# Schematic_v20.net
KiCad netlist of a schematic drawn in EAGLE
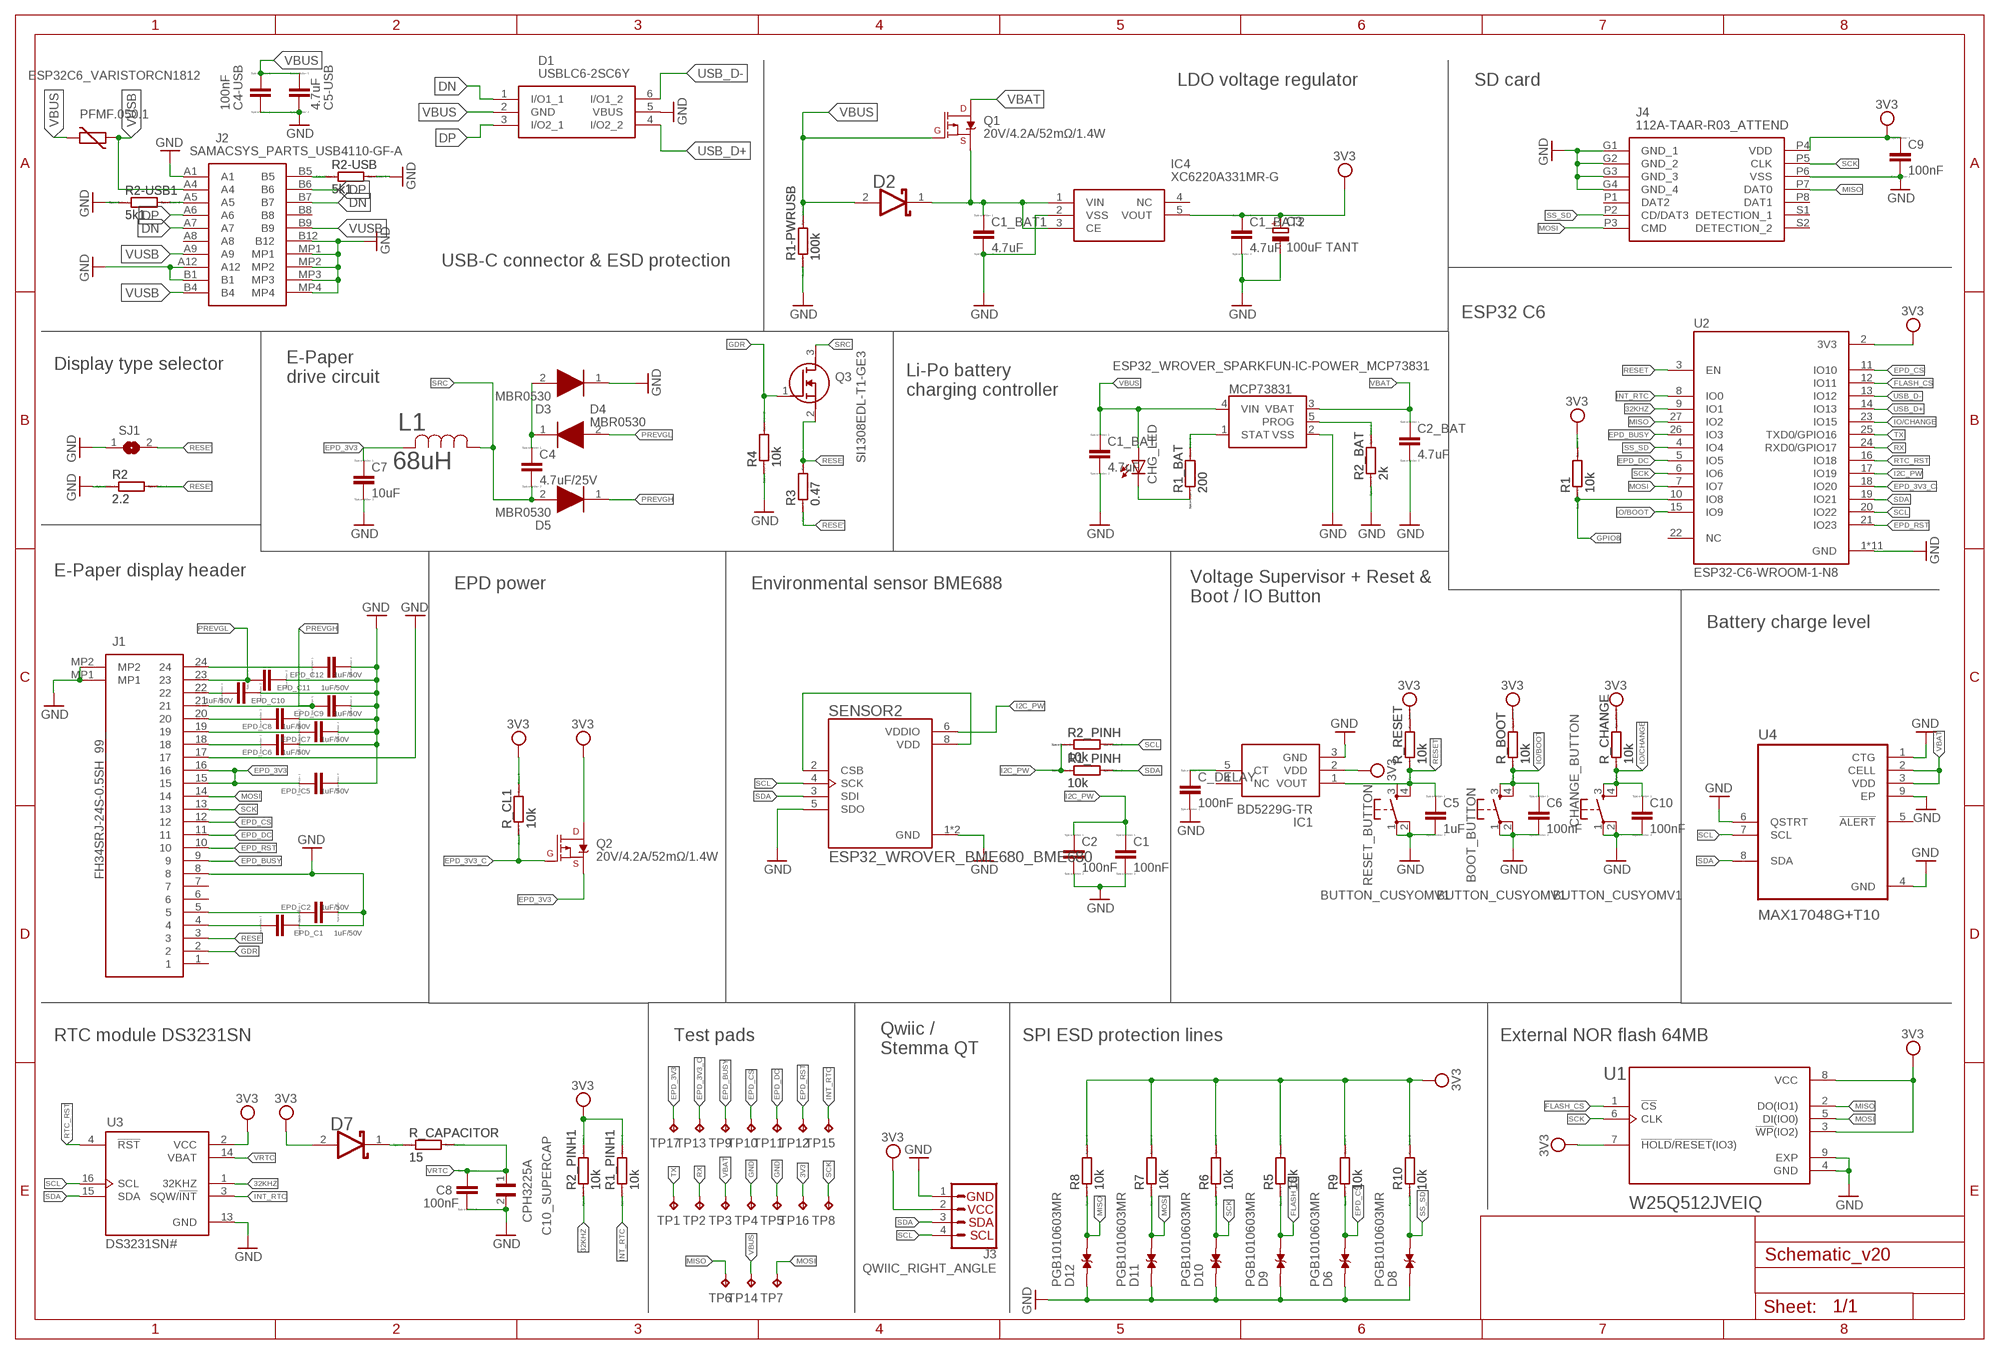
[diagram p0: schematic, sheet 1]

(export (version "E")
  (design (tool "Eeschema 10.0.6"))
  (components
    (comp (ref "BOOT_BUTTON")
      (value "BUTTON_CUSYOMV1")
      (footprint "eagle-import:MYBUTTON")
      (libsource (lib "eagle-import") (part "BUTTON_CUSYOMV1"))
    )
    (comp (ref "C1")
      (value "100nF")
      (footprint "eagle-import:EAGLE-LTSPICE_C0402")
      (libsource (lib "eagle-import") (part "EAGLE-LTSPICE_CC0402"))
    )
    (comp (ref "C1_BAT")
      (value "4.7uF")
      (footprint "eagle-import:EAGLE-LTSPICE_C0402")
      (libsource (lib "eagle-import") (part "EAGLE-LTSPICE_CC0402"))
    )
    (comp (ref "C1_BAT1")
      (value "4.7uF")
      (footprint "eagle-import:ESP32_WROVER_EAGLE-LTSPICE_C0402")
      (libsource (lib "eagle-import") (part "ESP32_WROVER_EAGLE-LTSPICE_CC0402"))
    )
    (comp (ref "C1_BAT2")
      (value "4.7uF")
      (footprint "eagle-import:ESP32_WROVER_EAGLE-LTSPICE_C0402")
      (libsource (lib "eagle-import") (part "ESP32_WROVER_EAGLE-LTSPICE_CC0402"))
    )
    (comp (ref "C2")
      (value "100nF")
      (footprint "eagle-import:EAGLE-LTSPICE_C0402")
      (libsource (lib "eagle-import") (part "EAGLE-LTSPICE_CC0402"))
    )
    (comp (ref "C2_BAT")
      (value "4.7uF")
      (footprint "eagle-import:EAGLE-LTSPICE_C0402")
      (libsource (lib "eagle-import") (part "EAGLE-LTSPICE_CC0402"))
    )
    (comp (ref "C3")
      (value "100uF TANT")
      (footprint "eagle-import:RCL_CT3528")
      (libsource (lib "eagle-import") (part "RCL_CPOL-EUCT3528"))
    )
    (comp (ref "C4")
      (value "4.7uF/25V")
      (footprint "eagle-import:EAGLE-LTSPICE_C0402")
      (libsource (lib "eagle-import") (part "EAGLE-LTSPICE_CC0402"))
    )
    (comp (ref "C4-USB")
      (value "100nF")
      (footprint "eagle-import:ESP32_WROVER_EAGLE-LTSPICE_C0402")
      (libsource (lib "eagle-import") (part "ESP32_WROVER_EAGLE-LTSPICE_CC0402"))
    )
    (comp (ref "C5")
      (value "1uF")
      (footprint "eagle-import:EAGLE-LTSPICE_C0402")
      (libsource (lib "eagle-import") (part "EAGLE-LTSPICE_CC0402"))
    )
    (comp (ref "C5-USB")
      (value "4.7uF")
      (footprint "eagle-import:ESP32_WROVER_EAGLE-LTSPICE_C0402")
      (libsource (lib "eagle-import") (part "ESP32_WROVER_EAGLE-LTSPICE_CC0402"))
    )
    (comp (ref "C6")
      (value "100nF")
      (footprint "eagle-import:EAGLE-LTSPICE_C0402")
      (libsource (lib "eagle-import") (part "EAGLE-LTSPICE_CC0402"))
    )
    (comp (ref "C7")
      (value "10uF")
      (footprint "eagle-import:EAGLE-LTSPICE_C0402")
      (libsource (lib "eagle-import") (part "EAGLE-LTSPICE_CC0402"))
    )
    (comp (ref "C8")
      (value "100nF")
      (footprint "eagle-import:EAGLE-LTSPICE_C0402")
      (libsource (lib "eagle-import") (part "EAGLE-LTSPICE_CC0402"))
    )
    (comp (ref "C9")
      (value "100nF")
      (footprint "eagle-import:EAGLE-LTSPICE_C0402")
      (libsource (lib "eagle-import") (part "EAGLE-LTSPICE_CC0402"))
    )
    (comp (ref "C10")
      (value "100nF")
      (footprint "eagle-import:EAGLE-LTSPICE_C0402")
      (libsource (lib "eagle-import") (part "EAGLE-LTSPICE_CC0402"))
    )
    (comp (ref "C10_SUPERCAP")
      (value "CPH3225A")
      (footprint "eagle-import:CAPCP3225X100N")
      (fields (field (name "MF") "Seiko Instruments"))
      (libsource (lib "eagle-import") (part "CPH3225A"))
    )
    (comp (ref "CHANGE_BUTTON")
      (value "BUTTON_CUSYOMV1")
      (footprint "eagle-import:MYBUTTON")
      (libsource (lib "eagle-import") (part "BUTTON_CUSYOMV1"))
    )
    (comp (ref "CHG_LED")
      (value "ADAFRUIT_LEDCHIP-LED0603")
      (footprint "eagle-import:ADAFRUIT_CHIP-LED0603")
      (libsource (lib "eagle-import") (part "ADAFRUIT_LEDCHIP-LED0603"))
    )
    (comp (ref "C_DELAY")
      (value "100nF")
      (footprint "eagle-import:EAGLE-LTSPICE_C0402")
      (libsource (lib "eagle-import") (part "EAGLE-LTSPICE_CC0402"))
    )
    (comp (ref "D1")
      (value "USBLC6-2SC6Y")
      (footprint "eagle-import:SOT95P280X145-6N")
      (fields (field (name "MF") "STMicroelectronics"))
      (libsource (lib "eagle-import") (part "USBLC6-2SC6Y"))
    )
    (comp (ref "D2")
      (value "ESP32_WROVER_AVX---SD0805S020S1R0_AVX_SD0805S020S1R0_0_0AVX_SD0805S020S1R0_0_0")
      (footprint "eagle-import:ESP32_WROVER_AVX---SD0805S020S1R0_AVX_SD0805S020S1R0_0")
      (fields
        (field (name "DIGIKEY_PART_NUMBER") "478-7800-1-ND")
        (field (name "MF") "AVX")
        (field (name "MOUSER_PART_NUMBER") "581-SD0805S020S1R0")
      )
      (libsource (lib "eagle-import") (part "ESP32_WROVER_AVX---SD0805S020S1R0_AVX_SD0805S020S1R0_0_0AVX_SD0805S020S1R0_0_0"))
    )
    (comp (ref "D3")
      (value "MBR0530")
      (footprint "eagle-import:SOD3716X135N")
      (fields (field (name "MF") "ON Semiconductor"))
      (libsource (lib "eagle-import") (part "MBR0530"))
    )
    (comp (ref "D4")
      (value "MBR0530")
      (footprint "eagle-import:SOD3716X135N")
      (fields (field (name "MF") "ON Semiconductor"))
      (libsource (lib "eagle-import") (part "MBR0530"))
    )
    (comp (ref "D5")
      (value "MBR0530")
      (footprint "eagle-import:SOD3716X135N")
      (fields (field (name "MF") "ON Semiconductor"))
      (libsource (lib "eagle-import") (part "MBR0530"))
    )
    (comp (ref "D6")
      (value "PGB1010603MR")
      (footprint "eagle-import:DIOC1608X36N")
      (fields (field (name "MF") "Littelfuse Inc."))
      (libsource (lib "eagle-import") (part "PGB1010603MR"))
    )
    (comp (ref "D7")
      (value "ESP32_WROVER_AVX---SD0805S020S1R0_AVX_SD0805S020S1R0_0_0AVX_SD0805S020S1R0_0_0")
      (footprint "eagle-import:ESP32_WROVER_AVX---SD0805S020S1R0_AVX_SD0805S020S1R0_0")
      (fields
        (field (name "DIGIKEY_PART_NUMBER") "478-7800-1-ND")
        (field (name "MF") "AVX")
        (field (name "MOUSER_PART_NUMBER") "581-SD0805S020S1R0")
      )
      (libsource (lib "eagle-import") (part "ESP32_WROVER_AVX---SD0805S020S1R0_AVX_SD0805S020S1R0_0_0AVX_SD0805S020S1R0_0_0"))
    )
    (comp (ref "D8")
      (value "PGB1010603MR")
      (footprint "eagle-import:DIOC1608X36N")
      (fields (field (name "MF") "Littelfuse Inc."))
      (libsource (lib "eagle-import") (part "PGB1010603MR"))
    )
    (comp (ref "D9")
      (value "PGB1010603MR")
      (footprint "eagle-import:DIOC1608X36N")
      (fields (field (name "MF") "Littelfuse Inc."))
      (libsource (lib "eagle-import") (part "PGB1010603MR"))
    )
    (comp (ref "D10")
      (value "PGB1010603MR")
      (footprint "eagle-import:DIOC1608X36N")
      (fields (field (name "MF") "Littelfuse Inc."))
      (libsource (lib "eagle-import") (part "PGB1010603MR"))
    )
    (comp (ref "D11")
      (value "PGB1010603MR")
      (footprint "eagle-import:DIOC1608X36N")
      (fields (field (name "MF") "Littelfuse Inc."))
      (libsource (lib "eagle-import") (part "PGB1010603MR"))
    )
    (comp (ref "D12")
      (value "PGB1010603MR")
      (footprint "eagle-import:DIOC1608X36N")
      (fields (field (name "MF") "Littelfuse Inc."))
      (libsource (lib "eagle-import") (part "PGB1010603MR"))
    )
    (comp (ref "EPD_C1")
      (value "1uF/50V")
      (footprint "eagle-import:EAGLE-LTSPICE_C0402")
      (libsource (lib "eagle-import") (part "EAGLE-LTSPICE_CC0402"))
    )
    (comp (ref "EPD_C2")
      (value "1uF/50V")
      (footprint "eagle-import:EAGLE-LTSPICE_C0402")
      (libsource (lib "eagle-import") (part "EAGLE-LTSPICE_CC0402"))
    )
    (comp (ref "EPD_C5")
      (value "1uF/50V")
      (footprint "eagle-import:EAGLE-LTSPICE_C0402")
      (libsource (lib "eagle-import") (part "EAGLE-LTSPICE_CC0402"))
    )
    (comp (ref "EPD_C6")
      (value "1uF/50V")
      (footprint "eagle-import:EAGLE-LTSPICE_C0402")
      (libsource (lib "eagle-import") (part "EAGLE-LTSPICE_CC0402"))
    )
    (comp (ref "EPD_C7")
      (value "1uF/50V")
      (footprint "eagle-import:EAGLE-LTSPICE_C0402")
      (libsource (lib "eagle-import") (part "EAGLE-LTSPICE_CC0402"))
    )
    (comp (ref "EPD_C8")
      (value "1uF/50V")
      (footprint "eagle-import:EAGLE-LTSPICE_C0402")
      (libsource (lib "eagle-import") (part "EAGLE-LTSPICE_CC0402"))
    )
    (comp (ref "EPD_C9")
      (value "1uF/50V")
      (footprint "eagle-import:EAGLE-LTSPICE_C0402")
      (libsource (lib "eagle-import") (part "EAGLE-LTSPICE_CC0402"))
    )
    (comp (ref "EPD_C10")
      (value "1uF/50V")
      (footprint "eagle-import:EAGLE-LTSPICE_C0402")
      (libsource (lib "eagle-import") (part "EAGLE-LTSPICE_CC0402"))
    )
    (comp (ref "EPD_C11")
      (value "1uF/50V")
      (footprint "eagle-import:EAGLE-LTSPICE_C0402")
      (libsource (lib "eagle-import") (part "EAGLE-LTSPICE_CC0402"))
    )
    (comp (ref "EPD_C12")
      (value "1uF/50V")
      (footprint "eagle-import:EAGLE-LTSPICE_C0402")
      (libsource (lib "eagle-import") (part "EAGLE-LTSPICE_CC0402"))
    )
    (comp (ref "IC1")
      (value "BD5229G-TR")
      (footprint "eagle-import:SOT95P280X125-5N")
      (fields (field (name "MOUSER_PART_NUMBER") "755-BD5229G-TR"))
      (libsource (lib "eagle-import") (part "BD5229G-TR"))
    )
    (comp (ref "IC4")
      (value "XC6220A331MR-G")
      (footprint "eagle-import:SOT95P280X120-5N")
      (fields (field (name "MOUSER_PART_NUMBER") "865-XC6220A331MR-G"))
      (libsource (lib "eagle-import") (part "XC6220A331MR-G"))
    )
    (comp (ref "J1")
      (value "FH34SRJ-24S-0.5SH_99_")
      (footprint "eagle-import:FH34SRJ24S05SH99")
      (fields
        (field (name "MANUFACTURER_PART_NUMBER") "FH34SRJ-24S-0.5SH(99)")
        (field (name "MOUSER_PART_NUMBER") "798-FH34SRJ24S05SH99")
      )
      (libsource (lib "eagle-import") (part "FH34SRJ-24S-0.5SH_99_"))
    )
    (comp (ref "J2")
      (value "SAMACSYS_PARTS_USB4110-GF-A")
      (footprint "eagle-import:SAMACSYS_PARTS_USB4110GFA")
      (fields
        (field (name "MANUFACTURER_PART_NUMBER") "USB4110-GF-A")
        (field (name "MOUSER_PART_NUMBER") "640-USB4110-GF-A")
      )
      (libsource (lib "eagle-import") (part "SAMACSYS_PARTS_USB4110-GF-A"))
    )
    (comp (ref "J3")
      (value "QWIIC_RIGHT_ANGLE")
      (footprint "eagle-import:JST04_1MM_RA")
      (libsource (lib "eagle-import") (part "QWIIC_CONNECTORJS-1MM"))
    )
    (comp (ref "J4")
      (value "112A-TAAR-R03_ATTEND")
      (footprint "eagle-import:112ATAARR03ATTEND")
      (fields (field (name "MANUFACTURER_PART_NUMBER") "112A-TAAR-R03 ATTEND"))
      (libsource (lib "eagle-import") (part "112A-TAAR-R03_ATTEND"))
    )
    (comp (ref "L1")
      (value "68uH")
      (footprint "eagle-import:IND_4828-WE-TPC_WRE")
      (fields
        (field (name "MANUFACTURER_PART_NUMBER") "744043680")
        (field (name "COPYRIGHT") "Copyright (C) 2024 Ultra Librarian. All rights reserved.")
      )
      (libsource (lib "eagle-import") (part "744043680IND_4828-WE-TPC_WRE"))
    )
    (comp (ref "MCP73831")
      (value "ESP32_WROVER_SPARKFUN-IC-POWER_MCP73831")
      (footprint "eagle-import:ESP32_WROVER_SPARKFUN-IC-POWER_SOT23-5")
      (libsource (lib "eagle-import") (part "ESP32_WROVER_SPARKFUN-IC-POWER_MCP73831"))
    )
    (comp (ref "PFMF.050.1")
      (value "ESP32C6_VARISTORCN1812")
      (footprint "eagle-import:ESP32C6_VARISTOR_CT_CN1812")
      (libsource (lib "eagle-import") (part "ESP32C6_VARISTORCN1812"))
    )
    (comp (ref "Q1")
      (value "20V/4.2A/52mΩ/1.4W")
      (footprint "eagle-import:ESP32_WROVER_SPARKFUN-DISCRETESEMI_SOT23-3")
      (libsource (lib "eagle-import") (part "ESP32_WROVER_SPARKFUN-DISCRETESEMI_MOSFET_PCH-DMG2305UX-7"))
    )
    (comp (ref "Q2")
      (value "20V/4.2A/52mΩ/1.4W")
      (footprint "eagle-import:ESP32_WROVER_SPARKFUN-DISCRETESEMI_SOT23-3")
      (libsource (lib "eagle-import") (part "ESP32_WROVER_SPARKFUN-DISCRETESEMI_MOSFET_PCH-DMG2305UX-7"))
    )
    (comp (ref "Q3")
      (value "SI1308EDL-T1-GE3")
      (footprint "eagle-import:SOT65P210X110-3N")
      (fields (field (name "MF") "Vishay Siliconix"))
      (libsource (lib "eagle-import") (part "SI1308EDL-T1-GE3"))
    )
    (comp (ref "R1")
      (value "10k")
      (footprint "eagle-import:ESP32_WROVER_EAGLE-LTSPICE_R0402")
      (libsource (lib "eagle-import") (part "ESP32_WROVER_EAGLE-LTSPICE_RR0402"))
    )
    (comp (ref "R1-PWRUSB")
      (value "100k")
      (footprint "eagle-import:ESP32_WROVER_EAGLE-LTSPICE_R0402")
      (libsource (lib "eagle-import") (part "ESP32_WROVER_EAGLE-LTSPICE_RR0402"))
    )
    (comp (ref "R1_BAT")
      (value "200")
      (footprint "eagle-import:ESP32_WROVER_EAGLE-LTSPICE_R0402")
      (libsource (lib "eagle-import") (part "ESP32_WROVER_EAGLE-LTSPICE_RR0402"))
    )
    (comp (ref "R1_PINH")
      (value "10k")
      (footprint "eagle-import:ESP32_WROVER_EAGLE-LTSPICE_R0402")
      (libsource (lib "eagle-import") (part "ESP32_WROVER_EAGLE-LTSPICE_RR0402"))
    )
    (comp (ref "R1_PINH1")
      (value "10k")
      (footprint "eagle-import:ESP32_WROVER_EAGLE-LTSPICE_R0402")
      (libsource (lib "eagle-import") (part "ESP32_WROVER_EAGLE-LTSPICE_RR0402"))
    )
    (comp (ref "R2")
      (value "2.2")
      (footprint "eagle-import:ESP32_WROVER_EAGLE-LTSPICE_R0402")
      (libsource (lib "eagle-import") (part "ESP32_WROVER_EAGLE-LTSPICE_RR0402"))
    )
    (comp (ref "R2-USB")
      (value "5k1")
      (footprint "eagle-import:ESP32_WROVER_EAGLE-LTSPICE_R0402")
      (libsource (lib "eagle-import") (part "ESP32_WROVER_EAGLE-LTSPICE_RR0402"))
    )
    (comp (ref "R2-USB1")
      (value "5k1")
      (footprint "eagle-import:ESP32_WROVER_EAGLE-LTSPICE_R0402")
      (libsource (lib "eagle-import") (part "ESP32_WROVER_EAGLE-LTSPICE_RR0402"))
    )
    (comp (ref "R2_BAT")
      (value "2k")
      (footprint "eagle-import:ESP32_WROVER_EAGLE-LTSPICE_R0402")
      (libsource (lib "eagle-import") (part "ESP32_WROVER_EAGLE-LTSPICE_RR0402"))
    )
    (comp (ref "R2_PINH")
      (value "10k")
      (footprint "eagle-import:ESP32_WROVER_EAGLE-LTSPICE_R0402")
      (libsource (lib "eagle-import") (part "ESP32_WROVER_EAGLE-LTSPICE_RR0402"))
    )
    (comp (ref "R2_PINH1")
      (value "10k")
      (footprint "eagle-import:ESP32_WROVER_EAGLE-LTSPICE_R0402")
      (libsource (lib "eagle-import") (part "ESP32_WROVER_EAGLE-LTSPICE_RR0402"))
    )
    (comp (ref "R3")
      (value "0.47")
      (footprint "eagle-import:ESP32_WROVER_EAGLE-LTSPICE_R0402")
      (libsource (lib "eagle-import") (part "ESP32_WROVER_EAGLE-LTSPICE_RR0402"))
    )
    (comp (ref "R4")
      (value "10k")
      (footprint "eagle-import:ESP32_WROVER_EAGLE-LTSPICE_R0402")
      (libsource (lib "eagle-import") (part "ESP32_WROVER_EAGLE-LTSPICE_RR0402"))
    )
    (comp (ref "R5")
      (value "10k")
      (footprint "eagle-import:ESP32_WROVER_EAGLE-LTSPICE_R0402")
      (libsource (lib "eagle-import") (part "ESP32_WROVER_EAGLE-LTSPICE_RR0402"))
    )
    (comp (ref "R6")
      (value "10k")
      (footprint "eagle-import:ESP32_WROVER_EAGLE-LTSPICE_R0402")
      (libsource (lib "eagle-import") (part "ESP32_WROVER_EAGLE-LTSPICE_RR0402"))
    )
    (comp (ref "R7")
      (value "10k")
      (footprint "eagle-import:ESP32_WROVER_EAGLE-LTSPICE_R0402")
      (libsource (lib "eagle-import") (part "ESP32_WROVER_EAGLE-LTSPICE_RR0402"))
    )
    (comp (ref "R8")
      (value "10k")
      (footprint "eagle-import:ESP32_WROVER_EAGLE-LTSPICE_R0402")
      (libsource (lib "eagle-import") (part "ESP32_WROVER_EAGLE-LTSPICE_RR0402"))
    )
    (comp (ref "R9")
      (value "10k")
      (footprint "eagle-import:ESP32_WROVER_EAGLE-LTSPICE_R0402")
      (libsource (lib "eagle-import") (part "ESP32_WROVER_EAGLE-LTSPICE_RR0402"))
    )
    (comp (ref "R10")
      (value "10k")
      (footprint "eagle-import:ESP32_WROVER_EAGLE-LTSPICE_R0402")
      (libsource (lib "eagle-import") (part "ESP32_WROVER_EAGLE-LTSPICE_RR0402"))
    )
    (comp (ref "RESET_BUTTON")
      (value "BUTTON_CUSYOMV1")
      (footprint "eagle-import:MYBUTTON")
      (libsource (lib "eagle-import") (part "BUTTON_CUSYOMV1"))
    )
    (comp (ref "R_BOOT")
      (value "10k")
      (footprint "eagle-import:ESP32_WROVER_EAGLE-LTSPICE_R0402")
      (libsource (lib "eagle-import") (part "ESP32_WROVER_EAGLE-LTSPICE_RR0402"))
    )
    (comp (ref "R_CAPACITOR")
      (value "15")
      (footprint "eagle-import:ESP32_WROVER_EAGLE-LTSPICE_R0402")
      (libsource (lib "eagle-import") (part "ESP32_WROVER_EAGLE-LTSPICE_RR0402"))
    )
    (comp (ref "R_CHANGE")
      (value "10k")
      (footprint "eagle-import:ESP32_WROVER_EAGLE-LTSPICE_R0402")
      (libsource (lib "eagle-import") (part "ESP32_WROVER_EAGLE-LTSPICE_RR0402"))
    )
    (comp (ref "R_CL1")
      (value "10k")
      (footprint "eagle-import:ESP32_WROVER_EAGLE-LTSPICE_R0402")
      (libsource (lib "eagle-import") (part "ESP32_WROVER_EAGLE-LTSPICE_RR0402"))
    )
    (comp (ref "R_RESET")
      (value "10k")
      (footprint "eagle-import:ESP32_WROVER_EAGLE-LTSPICE_R0402")
      (libsource (lib "eagle-import") (part "ESP32_WROVER_EAGLE-LTSPICE_RR0402"))
    )
    (comp (ref "SENSOR2")
      (value "ESP32_WROVER_BME680_BME680")
      (footprint "eagle-import:ESP32_WROVER_BME680_PSON80P300X300X100-8N")
      (fields (field (name "MF") "Bosch Sensortec") (field (name "MP") "BME680"))
      (libsource (lib "eagle-import") (part "ESP32_WROVER_BME680_BME680"))
    )
    (comp (ref "SJ1") (value "SJ") (footprint "eagle-import:SJ") (libsource (lib "eagle-import") (part "SJ")))
    (comp (ref "TP1")
      (value "TPTP20R")
      (footprint "eagle-import:TP20R")
      (libsource (lib "eagle-import") (part "TPTP20R"))
    )
    (comp (ref "TP2")
      (value "TPTP20R")
      (footprint "eagle-import:TP20R")
      (libsource (lib "eagle-import") (part "TPTP20R"))
    )
    (comp (ref "TP3")
      (value "TPTP20R")
      (footprint "eagle-import:TP20R")
      (libsource (lib "eagle-import") (part "TPTP20R"))
    )
    (comp (ref "TP4")
      (value "TPTP20R")
      (footprint "eagle-import:TP20R")
      (libsource (lib "eagle-import") (part "TPTP20R"))
    )
    (comp (ref "TP5")
      (value "TPTP20R")
      (footprint "eagle-import:TP20R")
      (libsource (lib "eagle-import") (part "TPTP20R"))
    )
    (comp (ref "TP6")
      (value "TPTP20R")
      (footprint "eagle-import:TP20R")
      (libsource (lib "eagle-import") (part "TPTP20R"))
    )
    (comp (ref "TP7")
      (value "TPTP20R")
      (footprint "eagle-import:TP20R")
      (libsource (lib "eagle-import") (part "TPTP20R"))
    )
    (comp (ref "TP8")
      (value "TPTP20R")
      (footprint "eagle-import:TP20R")
      (libsource (lib "eagle-import") (part "TPTP20R"))
    )
    (comp (ref "TP9")
      (value "TPTP20R")
      (footprint "eagle-import:TP20R")
      (libsource (lib "eagle-import") (part "TPTP20R"))
    )
    (comp (ref "TP10")
      (value "TPTP20R")
      (footprint "eagle-import:TP20R")
      (libsource (lib "eagle-import") (part "TPTP20R"))
    )
    (comp (ref "TP11")
      (value "TPTP20R")
      (footprint "eagle-import:TP20R")
      (libsource (lib "eagle-import") (part "TPTP20R"))
    )
    (comp (ref "TP12")
      (value "TPTP20R")
      (footprint "eagle-import:TP20R")
      (libsource (lib "eagle-import") (part "TPTP20R"))
    )
    (comp (ref "TP13")
      (value "TPTP20R")
      (footprint "eagle-import:TP20R")
      (libsource (lib "eagle-import") (part "TPTP20R"))
    )
    (comp (ref "TP14")
      (value "TPTP20R")
      (footprint "eagle-import:TP20R")
      (libsource (lib "eagle-import") (part "TPTP20R"))
    )
    (comp (ref "TP15")
      (value "TPTP20R")
      (footprint "eagle-import:TP20R")
      (libsource (lib "eagle-import") (part "TPTP20R"))
    )
    (comp (ref "TP16")
      (value "TPTP20R")
      (footprint "eagle-import:TP20R")
      (libsource (lib "eagle-import") (part "TPTP20R"))
    )
    (comp (ref "TP17")
      (value "TPTP20R")
      (footprint "eagle-import:TP20R")
      (libsource (lib "eagle-import") (part "TPTP20R"))
    )
    (comp (ref "U1")
      (value "W25Q512JVEIQ")
      (footprint "eagle-import:SON127P600X800X80-9N")
      (fields (field (name "MF") "Winbond Electronics"))
      (libsource (lib "eagle-import") (part "W25Q512JVEIQ"))
    )
    (comp (ref "U2")
      (value "ESP32-C6-WROOM-1-N8")
      (footprint "eagle-import:XCVR_ESP32-C6-WROOM-1-N8")
      (fields (field (name "MF") "Espressif Systems"))
      (libsource (lib "eagle-import") (part "ESP32-C6-WROOM-1-N8"))
    )
    (comp (ref "U3")
      (value "DS3231SN#")
      (footprint "eagle-import:SOIC127P1032X265-16N")
      (fields (field (name "MF") "Analog Devices"))
      (libsource (lib "eagle-import") (part "DS3231SN#"))
    )
    (comp (ref "U4")
      (value "MAX17048G+T10")
      (footprint "eagle-import:SON50P200X200X80-9N")
      (fields (field (name "MF") "Analog Devices"))
      (libsource (lib "eagle-import") (part "MAX17048G+T10"))
    )
  )
  (nets
    (net (code "1") (name "3V3") (class "Default")
      (node (ref "C1_BAT2") (pin "1") (pinfunction "1_1") (pintype "passive"))
      (node (ref "C3") (pin "+") (pinfunction "+_+") (pintype "passive"))
      (node (ref "C9") (pin "1") (pinfunction "1_1") (pintype "passive"))
      (node (ref "D7") (pin "2") (pinfunction "ANODE_2") (pintype "bidirectional"))
      (node (ref "IC1") (pin "2") (pinfunction "VDD_2") (pintype "bidirectional"))
      (node (ref "IC4") (pin "5") (pinfunction "VOUT_5") (pintype "bidirectional"))
      (node (ref "J3") (pin "2") (pinfunction "2_2") (pintype "power_in"))
      (node (ref "J4") (pin "P4") (pinfunction "VDD_P4") (pintype "bidirectional"))
      (node (ref "Q2") (pin "3") (pinfunction "D_3") (pintype "bidirectional"))
      (node (ref "R1") (pin "2") (pinfunction "2_2") (pintype "passive"))
      (node (ref "R10") (pin "2") (pinfunction "2_2") (pintype "passive"))
      (node (ref "R1_PINH1") (pin "2") (pinfunction "2_2") (pintype "passive"))
      (node (ref "R2_PINH1") (pin "2") (pinfunction "2_2") (pintype "passive"))
      (node (ref "R5") (pin "2") (pinfunction "2_2") (pintype "passive"))
      (node (ref "R6") (pin "2") (pinfunction "2_2") (pintype "passive"))
      (node (ref "R7") (pin "2") (pinfunction "2_2") (pintype "passive"))
      (node (ref "R8") (pin "2") (pinfunction "2_2") (pintype "passive"))
      (node (ref "R9") (pin "2") (pinfunction "2_2") (pintype "passive"))
      (node (ref "R_BOOT") (pin "2") (pinfunction "2_2") (pintype "passive"))
      (node (ref "R_CHANGE") (pin "2") (pinfunction "2_2") (pintype "passive"))
      (node (ref "R_CL1") (pin "2") (pinfunction "2_2") (pintype "passive"))
      (node (ref "R_RESET") (pin "2") (pinfunction "2_2") (pintype "passive"))
      (node (ref "TP16") (pin "TP") (pinfunction "TP_TP") (pintype "input"))
      (node (ref "U1") (pin "3") (pinfunction "~{WP}(IO2)_3") (pintype "bidirectional"))
      (node (ref "U1") (pin "7") (pinfunction "~{HOLD}/~{RESET}(IO3)_7") (pintype "bidirectional"))
      (node (ref "U1") (pin "8") (pinfunction "VCC_8") (pintype "power_in"))
      (node (ref "U2") (pin "2") (pinfunction "3V3_2") (pintype "power_in"))
      (node (ref "U3") (pin "2") (pinfunction "VCC_2") (pintype "power_in"))
    )
    (net (code "2") (name "32KHZ") (class "Default")
      (node (ref "R2_PINH1") (pin "1") (pinfunction "1_1") (pintype "passive"))
      (node (ref "U2") (pin "9") (pinfunction "IO1_9") (pintype "bidirectional"))
      (node (ref "U3") (pin "1") (pinfunction "32KHZ_1") (pintype "output"))
    )
    (net (code "3") (name "DN") (class "Default")
      (node (ref "D1") (pin "1") (pinfunction "I/O1_1_1") (pintype "bidirectional"))
      (node (ref "J2") (pin "A7") (pinfunction "A7_A7") (pintype "bidirectional"))
      (node (ref "J2") (pin "B7") (pinfunction "B7_B7") (pintype "bidirectional"))
    )
    (net (code "4") (name "DP") (class "Default")
      (node (ref "D1") (pin "3") (pinfunction "I/O2_1_3") (pintype "bidirectional"))
      (node (ref "J2") (pin "A6") (pinfunction "A6_A6") (pintype "bidirectional"))
      (node (ref "J2") (pin "B6") (pinfunction "B6_B6") (pintype "bidirectional"))
    )
    (net (code "5") (name "EPD_3V3") (class "Default")
      (node (ref "C7") (pin "1") (pinfunction "1_1") (pintype "passive"))
      (node (ref "EPD_C5") (pin "1") (pinfunction "1_1") (pintype "passive"))
      (node (ref "J1") (pin "15") (pinfunction "15_15") (pintype "bidirectional"))
      (node (ref "J1") (pin "16") (pinfunction "16_16") (pintype "bidirectional"))
      (node (ref "L1") (pin "2") (pinfunction "2_2") (pintype "passive"))
      (node (ref "Q2") (pin "2") (pinfunction "S_2") (pintype "bidirectional"))
      (node (ref "TP17") (pin "TP") (pinfunction "TP_TP") (pintype "input"))
    )
    (net (code "6") (name "EPD_3V3_C") (class "Default")
      (node (ref "Q2") (pin "1") (pinfunction "G_1") (pintype "bidirectional"))
      (node (ref "R_CL1") (pin "1") (pinfunction "1_1") (pintype "passive"))
      (node (ref "TP13") (pin "TP") (pinfunction "TP_TP") (pintype "input"))
      (node (ref "U2") (pin "18") (pinfunction "IO20_18") (pintype "bidirectional"))
    )
    (net (code "7") (name "EPD_BUSY") (class "Default")
      (node (ref "J1") (pin "9") (pinfunction "9_9") (pintype "bidirectional"))
      (node (ref "TP9") (pin "TP") (pinfunction "TP_TP") (pintype "input"))
      (node (ref "U2") (pin "26") (pinfunction "IO3_26") (pintype "bidirectional"))
    )
    (net (code "8") (name "EPD_CS") (class "Default")
      (node (ref "D6") (pin "2") (pinfunction "2_2") (pintype "passive"))
      (node (ref "J1") (pin "12") (pinfunction "12_12") (pintype "bidirectional"))
      (node (ref "R9") (pin "1") (pinfunction "1_1") (pintype "passive"))
      (node (ref "TP10") (pin "TP") (pinfunction "TP_TP") (pintype "input"))
      (node (ref "U2") (pin "11") (pinfunction "IO10_11") (pintype "bidirectional"))
    )
    (net (code "9") (name "EPD_DC") (class "Default")
      (node (ref "J1") (pin "11") (pinfunction "11_11") (pintype "bidirectional"))
      (node (ref "TP11") (pin "TP") (pinfunction "TP_TP") (pintype "input"))
      (node (ref "U2") (pin "5") (pinfunction "IO5_5") (pintype "bidirectional"))
    )
    (net (code "10") (name "EPD_RST") (class "Default")
      (node (ref "J1") (pin "10") (pinfunction "10_10") (pintype "bidirectional"))
      (node (ref "TP12") (pin "TP") (pinfunction "TP_TP") (pintype "input"))
      (node (ref "U2") (pin "21") (pinfunction "IO23_21") (pintype "bidirectional"))
    )
    (net (code "11") (name "FLASH_CS") (class "Default")
      (node (ref "D9") (pin "2") (pinfunction "2_2") (pintype "passive"))
      (node (ref "R5") (pin "1") (pinfunction "1_1") (pintype "passive"))
      (node (ref "U1") (pin "1") (pinfunction "~{CS}_1") (pintype "input"))
      (node (ref "U2") (pin "12") (pinfunction "IO11_12") (pintype "bidirectional"))
    )
    (net (code "12") (name "GDR") (class "Default")
      (node (ref "J1") (pin "2") (pinfunction "2_2") (pintype "bidirectional"))
      (node (ref "Q3") (pin "1") (pinfunction "G_1") (pintype "bidirectional"))
      (node (ref "R4") (pin "2") (pinfunction "2_2") (pintype "passive"))
    )
    (net (code "13") (name "GND") (class "Default")
      (node (ref "BOOT_BUTTON") (pin "1") (pinfunction "1_1") (pintype "passive"))
      (node (ref "BOOT_BUTTON") (pin "2") (pinfunction "2_2") (pintype "passive"))
      (node (ref "C1") (pin "2") (pinfunction "2_2") (pintype "passive"))
      (node (ref "C10") (pin "2") (pinfunction "2_2") (pintype "passive"))
      (node (ref "C10_SUPERCAP") (pin "2") (pinfunction "2_2") (pintype "passive"))
      (node (ref "C1_BAT") (pin "2") (pinfunction "2_2") (pintype "passive"))
      (node (ref "C1_BAT1") (pin "2") (pinfunction "2_2") (pintype "passive"))
      (node (ref "C1_BAT2") (pin "2") (pinfunction "2_2") (pintype "passive"))
      (node (ref "C2") (pin "2") (pinfunction "2_2") (pintype "passive"))
      (node (ref "C2_BAT") (pin "2") (pinfunction "2_2") (pintype "passive"))
      (node (ref "C3") (pin "-") (pinfunction "-_-") (pintype "passive"))
      (node (ref "C4-USB") (pin "2") (pinfunction "2_2") (pintype "passive"))
      (node (ref "C5") (pin "2") (pinfunction "2_2") (pintype "passive"))
      (node (ref "C5-USB") (pin "2") (pinfunction "2_2") (pintype "passive"))
      (node (ref "C6") (pin "2") (pinfunction "2_2") (pintype "passive"))
      (node (ref "C7") (pin "2") (pinfunction "2_2") (pintype "passive"))
      (node (ref "C8") (pin "2") (pinfunction "2_2") (pintype "passive"))
      (node (ref "C9") (pin "2") (pinfunction "2_2") (pintype "passive"))
      (node (ref "CHANGE_BUTTON") (pin "1") (pinfunction "1_1") (pintype "passive"))
      (node (ref "CHANGE_BUTTON") (pin "2") (pinfunction "2_2") (pintype "passive"))
      (node (ref "C_DELAY") (pin "2") (pinfunction "2_2") (pintype "passive"))
      (node (ref "D1") (pin "5") (pinfunction "VBUS_5") (pintype "bidirectional"))
      (node (ref "D10") (pin "1") (pinfunction "1_1") (pintype "passive"))
      (node (ref "D11") (pin "1") (pinfunction "1_1") (pintype "passive"))
      (node (ref "D12") (pin "1") (pinfunction "1_1") (pintype "passive"))
      (node (ref "D3") (pin "1") (pinfunction "K_1") (pintype "bidirectional"))
      (node (ref "D6") (pin "1") (pinfunction "1_1") (pintype "passive"))
      (node (ref "D8") (pin "1") (pinfunction "1_1") (pintype "passive"))
      (node (ref "D9") (pin "1") (pinfunction "1_1") (pintype "passive"))
      (node (ref "EPD_C1") (pin "2") (pinfunction "2_2") (pintype "passive"))
      (node (ref "EPD_C10") (pin "2") (pinfunction "2_2") (pintype "passive"))
      (node (ref "EPD_C11") (pin "2") (pinfunction "2_2") (pintype "passive"))
      (node (ref "EPD_C12") (pin "2") (pinfunction "2_2") (pintype "passive"))
      (node (ref "EPD_C2") (pin "2") (pinfunction "2_2") (pintype "passive"))
      (node (ref "EPD_C5") (pin "2") (pinfunction "2_2") (pintype "passive"))
      (node (ref "EPD_C6") (pin "2") (pinfunction "2_2") (pintype "passive"))
      (node (ref "EPD_C7") (pin "2") (pinfunction "2_2") (pintype "passive"))
      (node (ref "EPD_C8") (pin "2") (pinfunction "2_2") (pintype "passive"))
      (node (ref "EPD_C9") (pin "2") (pinfunction "2_2") (pintype "passive"))
      (node (ref "IC1") (pin "3") (pinfunction "GND_3") (pintype "bidirectional"))
      (node (ref "IC4") (pin "2") (pinfunction "VSS_2") (pintype "bidirectional"))
      (node (ref "J1") (pin "17") (pinfunction "17_17") (pintype "bidirectional"))
      (node (ref "J1") (pin "8") (pinfunction "8_8") (pintype "bidirectional"))
      (node (ref "J1") (pin "MP1") (pinfunction "MP1_MP1") (pintype "bidirectional"))
      (node (ref "J1") (pin "MP2") (pinfunction "MP2_MP2") (pintype "bidirectional"))
      (node (ref "J2") (pin "A1") (pinfunction "A1_A1") (pintype "bidirectional"))
      (node (ref "J2") (pin "A12") (pinfunction "A12_A12") (pintype "bidirectional"))
      (node (ref "J2") (pin "B1") (pinfunction "B1_B1") (pintype "bidirectional"))
      (node (ref "J2") (pin "B12") (pinfunction "B12_B12") (pintype "bidirectional"))
      (node (ref "J2") (pin "MP1") (pinfunction "MP1_MP1") (pintype "bidirectional"))
      (node (ref "J2") (pin "MP2") (pinfunction "MP2_MP2") (pintype "bidirectional"))
      (node (ref "J2") (pin "MP3") (pinfunction "MP3_MP3") (pintype "bidirectional"))
      (node (ref "J2") (pin "MP4") (pinfunction "MP4_MP4") (pintype "bidirectional"))
      (node (ref "J3") (pin "1") (pinfunction "1_1") (pintype "power_in"))
      (node (ref "J4") (pin "G1") (pinfunction "GND_1_G1") (pintype "bidirectional"))
      (node (ref "J4") (pin "G2") (pinfunction "GND_2_G2") (pintype "bidirectional"))
      (node (ref "J4") (pin "G3") (pinfunction "GND_3_G3") (pintype "bidirectional"))
      (node (ref "J4") (pin "G4") (pinfunction "GND_4_G4") (pintype "bidirectional"))
      (node (ref "J4") (pin "P6") (pinfunction "VSS_P6") (pintype "bidirectional"))
      (node (ref "MCP73831") (pin "2") (pinfunction "VSS_2") (pintype "power_in"))
      (node (ref "R1-PWRUSB") (pin "1") (pinfunction "1_1") (pintype "passive"))
      (node (ref "R2") (pin "1") (pinfunction "1_1") (pintype "passive"))
      (node (ref "R2-USB") (pin "2") (pinfunction "2_2") (pintype "passive"))
      (node (ref "R2-USB1") (pin "1") (pinfunction "1_1") (pintype "passive"))
      (node (ref "R2_BAT") (pin "1") (pinfunction "1_1") (pintype "passive"))
      (node (ref "R4") (pin "1") (pinfunction "1_1") (pintype "passive"))
      (node (ref "RESET_BUTTON") (pin "1") (pinfunction "1_1") (pintype "passive"))
      (node (ref "RESET_BUTTON") (pin "2") (pinfunction "2_2") (pintype "passive"))
      (node (ref "SENSOR2") (pin "1") (pinfunction "GND_1") (pintype "power_in"))
      (node (ref "SENSOR2") (pin "5") (pinfunction "SDO_5") (pintype "bidirectional"))
      (node (ref "SENSOR2") (pin "7") (pinfunction "GND_7") (pintype "power_in"))
      (node (ref "SJ1") (pin "1") (pinfunction "1_1") (pintype "passive"))
      (node (ref "TP4") (pin "TP") (pinfunction "TP_TP") (pintype "input"))
      (node (ref "TP5") (pin "TP") (pinfunction "TP_TP") (pintype "input"))
      (node (ref "U1") (pin "4") (pinfunction "GND_4") (pintype "power_in"))
      (node (ref "U1") (pin "9") (pinfunction "EXP_9") (pintype "passive"))
      (node (ref "U2") (pin "1") (pinfunction "GND_1") (pintype "power_in"))
      (node (ref "U2") (pin "28") (pinfunction "GND_28") (pintype "power_in"))
      (node (ref "U2") (pin "29_1") (pinfunction "GND_29_1") (pintype "power_in"))
      (node (ref "U2") (pin "29_2") (pinfunction "GND_29_2") (pintype "power_in"))
      (node (ref "U2") (pin "29_3") (pinfunction "GND_29_3") (pintype "power_in"))
      (node (ref "U2") (pin "29_4") (pinfunction "GND_29_4") (pintype "power_in"))
      (node (ref "U2") (pin "29_5") (pinfunction "GND_29_5") (pintype "power_in"))
      (node (ref "U2") (pin "29_6") (pinfunction "GND_29_6") (pintype "power_in"))
      (node (ref "U2") (pin "29_7") (pinfunction "GND_29_7") (pintype "power_in"))
      (node (ref "U2") (pin "29_8") (pinfunction "GND_29_8") (pintype "power_in"))
      (node (ref "U2") (pin "29_9") (pinfunction "GND_29_9") (pintype "power_in"))
      (node (ref "U3") (pin "13") (pinfunction "GND_13") (pintype "power_in"))
      (node (ref "U4") (pin "1") (pinfunction "CTG_1") (pintype "power_in"))
      (node (ref "U4") (pin "4") (pinfunction "GND_4") (pintype "power_in"))
      (node (ref "U4") (pin "6") (pinfunction "QSTRT_6") (pintype "input"))
      (node (ref "U4") (pin "9") (pinfunction "EP_9") (pintype "power_in"))
    )
    (net (code "14") (name "GPIO8") (class "Default")
      (node (ref "R1") (pin "1") (pinfunction "1_1") (pintype "passive"))
      (node (ref "U2") (pin "10") (pinfunction "IO8_10") (pintype "bidirectional"))
    )
    (net (code "15") (name "I2C_PW") (class "Default")
      (node (ref "C1") (pin "1") (pinfunction "1_1") (pintype "passive"))
      (node (ref "C2") (pin "1") (pinfunction "1_1") (pintype "passive"))
      (node (ref "R1_PINH") (pin "1") (pinfunction "1_1") (pintype "passive"))
      (node (ref "R2_PINH") (pin "1") (pinfunction "1_1") (pintype "passive"))
      (node (ref "SENSOR2") (pin "6") (pinfunction "VDDIO_6") (pintype "power_in"))
      (node (ref "U2") (pin "17") (pinfunction "IO19_17") (pintype "bidirectional"))
    )
    (net (code "16") (name "INT_RTC") (class "Default")
      (node (ref "R1_PINH1") (pin "1") (pinfunction "1_1") (pintype "passive"))
      (node (ref "TP15") (pin "TP") (pinfunction "TP_TP") (pintype "input"))
      (node (ref "U2") (pin "8") (pinfunction "IO0_8") (pintype "bidirectional"))
      (node (ref "U3") (pin "3") (pinfunction "SQW/~{INT}_3") (pintype "output"))
    )
    (net (code "17") (name "IO{slash}BOOT") (class "Default")
      (node (ref "BOOT_BUTTON") (pin "3") (pinfunction "3_3") (pintype "passive"))
      (node (ref "BOOT_BUTTON") (pin "4") (pinfunction "4_4") (pintype "passive"))
      (node (ref "C6") (pin "1") (pinfunction "1_1") (pintype "passive"))
      (node (ref "R_BOOT") (pin "1") (pinfunction "1_1") (pintype "passive"))
      (node (ref "U2") (pin "15") (pinfunction "IO9_15") (pintype "bidirectional"))
    )
    (net (code "18") (name "IO{slash}CHANGE") (class "Default")
      (node (ref "C10") (pin "1") (pinfunction "1_1") (pintype "passive"))
      (node (ref "CHANGE_BUTTON") (pin "3") (pinfunction "3_3") (pintype "passive"))
      (node (ref "CHANGE_BUTTON") (pin "4") (pinfunction "4_4") (pintype "passive"))
      (node (ref "R_CHANGE") (pin "1") (pinfunction "1_1") (pintype "passive"))
      (node (ref "U2") (pin "23") (pinfunction "IO15_23") (pintype "bidirectional"))
    )
    (net (code "19") (name "MISO") (class "Default")
      (node (ref "D12") (pin "2") (pinfunction "2_2") (pintype "passive"))
      (node (ref "J4") (pin "P7") (pinfunction "DAT0_P7") (pintype "bidirectional"))
      (node (ref "R8") (pin "1") (pinfunction "1_1") (pintype "passive"))
      (node (ref "TP6") (pin "TP") (pinfunction "TP_TP") (pintype "input"))
      (node (ref "U1") (pin "2") (pinfunction "DO(IO1)_2") (pintype "bidirectional"))
      (node (ref "U2") (pin "27") (pinfunction "IO2_27") (pintype "bidirectional"))
    )
    (net (code "20") (name "MOSI") (class "Default")
      (node (ref "D11") (pin "2") (pinfunction "2_2") (pintype "passive"))
      (node (ref "J1") (pin "14") (pinfunction "14_14") (pintype "bidirectional"))
      (node (ref "J4") (pin "P3") (pinfunction "CMD_P3") (pintype "bidirectional"))
      (node (ref "R7") (pin "1") (pinfunction "1_1") (pintype "passive"))
      (node (ref "TP7") (pin "TP") (pinfunction "TP_TP") (pintype "input"))
      (node (ref "U1") (pin "5") (pinfunction "DI(IO0)_5") (pintype "bidirectional"))
      (node (ref "U2") (pin "7") (pinfunction "IO7_7") (pintype "bidirectional"))
    )
    (net (code "21") (name "Net-(CHG_LED-PadC)") (class "Default")
      (node (ref "CHG_LED") (pin "C") (pinfunction "C_C") (pintype "passive"))
      (node (ref "R1_BAT") (pin "1") (pinfunction "1_1") (pintype "passive"))
    )
    (net (code "22") (name "Net-(D2-CATHODE)") (class "Default")
      (node (ref "C1_BAT1") (pin "1") (pinfunction "1_1") (pintype "passive"))
      (node (ref "D2") (pin "1") (pinfunction "CATHODE_1") (pintype "bidirectional"))
      (node (ref "IC4") (pin "1") (pinfunction "VIN_1") (pintype "bidirectional"))
      (node (ref "IC4") (pin "3") (pinfunction "CE_3") (pintype "bidirectional"))
      (node (ref "Q1") (pin "2") (pinfunction "S_2") (pintype "bidirectional"))
    )
    (net (code "23") (name "Net-(D3-A)") (class "Default")
      (node (ref "C4") (pin "1") (pinfunction "1_1") (pintype "passive"))
      (node (ref "D3") (pin "2") (pinfunction "A_2") (pintype "bidirectional"))
      (node (ref "D4") (pin "1") (pinfunction "K_1") (pintype "bidirectional"))
    )
    (net (code "24") (name "Net-(D7-CATHODE)") (class "Default")
      (node (ref "D7") (pin "1") (pinfunction "CATHODE_1") (pintype "bidirectional"))
      (node (ref "R_CAPACITOR") (pin "1") (pinfunction "1_1") (pintype "passive"))
    )
    (net (code "25") (name "Net-(EPD_C1-Pad1)") (class "Default")
      (node (ref "EPD_C1") (pin "1") (pinfunction "1_1") (pintype "passive"))
      (node (ref "J1") (pin "4") (pinfunction "4_4") (pintype "bidirectional"))
    )
    (net (code "26") (name "Net-(EPD_C2-Pad1)") (class "Default")
      (node (ref "EPD_C2") (pin "1") (pinfunction "1_1") (pintype "passive"))
      (node (ref "J1") (pin "5") (pinfunction "5_5") (pintype "bidirectional"))
    )
    (net (code "27") (name "Net-(EPD_C6-Pad1)") (class "Default")
      (node (ref "EPD_C6") (pin "1") (pinfunction "1_1") (pintype "passive"))
      (node (ref "J1") (pin "18") (pinfunction "18_18") (pintype "bidirectional"))
    )
    (net (code "28") (name "Net-(EPD_C7-Pad1)") (class "Default")
      (node (ref "EPD_C7") (pin "1") (pinfunction "1_1") (pintype "passive"))
      (node (ref "J1") (pin "19") (pinfunction "19_19") (pintype "bidirectional"))
    )
    (net (code "29") (name "Net-(EPD_C8-Pad1)") (class "Default")
      (node (ref "EPD_C8") (pin "1") (pinfunction "1_1") (pintype "passive"))
      (node (ref "J1") (pin "20") (pinfunction "20_20") (pintype "bidirectional"))
    )
    (net (code "30") (name "Net-(EPD_C10-Pad1)") (class "Default")
      (node (ref "EPD_C10") (pin "1") (pinfunction "1_1") (pintype "passive"))
      (node (ref "J1") (pin "22") (pinfunction "22_22") (pintype "bidirectional"))
    )
    (net (code "31") (name "Net-(EPD_C12-Pad1)") (class "Default")
      (node (ref "EPD_C12") (pin "1") (pinfunction "1_1") (pintype "passive"))
      (node (ref "J1") (pin "24") (pinfunction "24_24") (pintype "bidirectional"))
    )
    (net (code "32") (name "Net-(IC1-CT)") (class "Default")
      (node (ref "C_DELAY") (pin "1") (pinfunction "1_1") (pintype "passive"))
      (node (ref "IC1") (pin "5") (pinfunction "CT_5") (pintype "bidirectional"))
    )
    (net (code "33") (name "Net-(J2-PadA5)") (class "Default")
      (node (ref "J2") (pin "A5") (pinfunction "A5_A5") (pintype "bidirectional"))
      (node (ref "R2-USB1") (pin "2") (pinfunction "2_2") (pintype "passive"))
    )
    (net (code "34") (name "Net-(J2-PadB5)") (class "Default")
      (node (ref "J2") (pin "B5") (pinfunction "B5_B5") (pintype "bidirectional"))
      (node (ref "R2-USB") (pin "1") (pinfunction "1_1") (pintype "passive"))
    )
    (net (code "35") (name "Net-(MCP73831-PROG)") (class "Default")
      (node (ref "MCP73831") (pin "5") (pinfunction "PROG_5") (pintype "input"))
      (node (ref "R2_BAT") (pin "2") (pinfunction "2_2") (pintype "passive"))
    )
    (net (code "36") (name "Net-(MCP73831-STAT)") (class "Default")
      (node (ref "MCP73831") (pin "1") (pinfunction "STAT_1") (pintype "output"))
      (node (ref "R1_BAT") (pin "2") (pinfunction "2_2") (pintype "passive"))
    )
    (net (code "37") (name "Net-(SENSOR2-CSB)") (class "Default")
      (node (ref "SENSOR2") (pin "2") (pinfunction "CSB_2") (pintype "input"))
      (node (ref "SENSOR2") (pin "8") (pinfunction "VDD_8") (pintype "power_in"))
    )
    (net (code "38") (name "PREVGH") (class "Default")
      (node (ref "D5") (pin "1") (pinfunction "K_1") (pintype "bidirectional"))
      (node (ref "EPD_C9") (pin "1") (pinfunction "1_1") (pintype "passive"))
      (node (ref "J1") (pin "21") (pinfunction "21_21") (pintype "bidirectional"))
    )
    (net (code "39") (name "PREVGL") (class "Default")
      (node (ref "D4") (pin "2") (pinfunction "A_2") (pintype "bidirectional"))
      (node (ref "EPD_C11") (pin "1") (pinfunction "1_1") (pintype "passive"))
      (node (ref "J1") (pin "23") (pinfunction "23_23") (pintype "bidirectional"))
    )
    (net (code "40") (name "RESE") (class "Default")
      (node (ref "J1") (pin "3") (pinfunction "3_3") (pintype "bidirectional"))
      (node (ref "Q3") (pin "2") (pinfunction "S_2") (pintype "bidirectional"))
      (node (ref "R3") (pin "2") (pinfunction "2_2") (pintype "passive"))
    )
    (net (code "41") (name "RESE'") (class "Default")
      (node (ref "R2") (pin "2") (pinfunction "2_2") (pintype "passive"))
      (node (ref "R3") (pin "1") (pinfunction "1_1") (pintype "passive"))
      (node (ref "SJ1") (pin "2") (pinfunction "2_2") (pintype "passive"))
    )
    (net (code "42") (name "RESET") (class "Default")
      (node (ref "C5") (pin "1") (pinfunction "1_1") (pintype "passive"))
      (node (ref "IC1") (pin "1") (pinfunction "VOUT_1") (pintype "bidirectional"))
      (node (ref "RESET_BUTTON") (pin "3") (pinfunction "3_3") (pintype "passive"))
      (node (ref "RESET_BUTTON") (pin "4") (pinfunction "4_4") (pintype "passive"))
      (node (ref "R_RESET") (pin "1") (pinfunction "1_1") (pintype "passive"))
      (node (ref "U2") (pin "3") (pinfunction "EN_3") (pintype "input"))
    )
    (net (code "43") (name "RTC_RST") (class "Default")
      (node (ref "U2") (pin "16") (pinfunction "IO18_16") (pintype "bidirectional"))
      (node (ref "U3") (pin "4") (pinfunction "~{RST}_4") (pintype "input"))
    )
    (net (code "44") (name "RX") (class "Default")
      (node (ref "TP2") (pin "TP") (pinfunction "TP_TP") (pintype "input"))
      (node (ref "U2") (pin "24") (pinfunction "RXD0/GPIO17_24") (pintype "bidirectional"))
    )
    (net (code "45") (name "SCK") (class "Default")
      (node (ref "D10") (pin "2") (pinfunction "2_2") (pintype "passive"))
      (node (ref "J1") (pin "13") (pinfunction "13_13") (pintype "bidirectional"))
      (node (ref "J4") (pin "P5") (pinfunction "CLK_P5") (pintype "bidirectional"))
      (node (ref "R6") (pin "1") (pinfunction "1_1") (pintype "passive"))
      (node (ref "TP8") (pin "TP") (pinfunction "TP_TP") (pintype "input"))
      (node (ref "U1") (pin "6") (pinfunction "CLK_6") (pintype "input"))
      (node (ref "U2") (pin "6") (pinfunction "IO6_6") (pintype "bidirectional"))
    )
    (net (code "46") (name "SCL") (class "Default")
      (node (ref "J3") (pin "4") (pinfunction "4_4") (pintype "passive"))
      (node (ref "R2_PINH") (pin "2") (pinfunction "2_2") (pintype "passive"))
      (node (ref "SENSOR2") (pin "4") (pinfunction "SCK_4") (pintype "input"))
      (node (ref "U2") (pin "20") (pinfunction "IO22_20") (pintype "bidirectional"))
      (node (ref "U3") (pin "16") (pinfunction "SCL_16") (pintype "input"))
      (node (ref "U4") (pin "7") (pinfunction "SCL_7") (pintype "input"))
    )
    (net (code "47") (name "SDA") (class "Default")
      (node (ref "J3") (pin "3") (pinfunction "3_3") (pintype "passive"))
      (node (ref "R1_PINH") (pin "2") (pinfunction "2_2") (pintype "passive"))
      (node (ref "SENSOR2") (pin "3") (pinfunction "SDI_3") (pintype "bidirectional"))
      (node (ref "U2") (pin "19") (pinfunction "IO21_19") (pintype "bidirectional"))
      (node (ref "U3") (pin "15") (pinfunction "SDA_15") (pintype "bidirectional"))
      (node (ref "U4") (pin "8") (pinfunction "SDA_8") (pintype "bidirectional"))
    )
    (net (code "48") (name "SRC") (class "Default")
      (node (ref "C4") (pin "2") (pinfunction "2_2") (pintype "passive"))
      (node (ref "D5") (pin "2") (pinfunction "A_2") (pintype "bidirectional"))
      (node (ref "L1") (pin "1") (pinfunction "1_1") (pintype "passive"))
      (node (ref "Q3") (pin "3") (pinfunction "D_3") (pintype "bidirectional"))
    )
    (net (code "49") (name "SS_SD") (class "Default")
      (node (ref "D8") (pin "2") (pinfunction "2_2") (pintype "passive"))
      (node (ref "J4") (pin "P2") (pinfunction "CD/DAT3_P2") (pintype "bidirectional"))
      (node (ref "R10") (pin "1") (pinfunction "1_1") (pintype "passive"))
      (node (ref "U2") (pin "4") (pinfunction "IO4_4") (pintype "bidirectional"))
    )
    (net (code "50") (name "TX") (class "Default")
      (node (ref "TP1") (pin "TP") (pinfunction "TP_TP") (pintype "input"))
      (node (ref "U2") (pin "25") (pinfunction "TXD0/GPIO16_25") (pintype "bidirectional"))
    )
    (net (code "51") (name "USB_D+") (class "Default")
      (node (ref "D1") (pin "4") (pinfunction "I/O2_2_4") (pintype "bidirectional"))
      (node (ref "U2") (pin "14") (pinfunction "IO13_14") (pintype "bidirectional"))
    )
    (net (code "52") (name "USB_D-") (class "Default")
      (node (ref "D1") (pin "6") (pinfunction "I/O1_2_6") (pintype "bidirectional"))
      (node (ref "U2") (pin "13") (pinfunction "IO12_13") (pintype "bidirectional"))
    )
    (net (code "53") (name "VBAT") (class "Default")
      (node (ref "C2_BAT") (pin "1") (pinfunction "1_1") (pintype "passive"))
      (node (ref "MCP73831") (pin "3") (pinfunction "VBAT_3") (pintype "power_in"))
      (node (ref "Q1") (pin "3") (pinfunction "D_3") (pintype "bidirectional"))
      (node (ref "TP3") (pin "TP") (pinfunction "TP_TP") (pintype "input"))
      (node (ref "U4") (pin "2") (pinfunction "CELL_2") (pintype "power_in"))
      (node (ref "U4") (pin "3") (pinfunction "VDD_3") (pintype "power_in"))
    )
    (net (code "54") (name "VBUS") (class "Default")
      (node (ref "C1_BAT") (pin "1") (pinfunction "1_1") (pintype "passive"))
      (node (ref "C4-USB") (pin "1") (pinfunction "1_1") (pintype "passive"))
      (node (ref "C5-USB") (pin "1") (pinfunction "1_1") (pintype "passive"))
      (node (ref "CHG_LED") (pin "A") (pinfunction "A_A") (pintype "passive"))
      (node (ref "D1") (pin "2") (pinfunction "GND_2") (pintype "bidirectional"))
      (node (ref "D2") (pin "2") (pinfunction "ANODE_2") (pintype "bidirectional"))
      (node (ref "MCP73831") (pin "4") (pinfunction "VIN_4") (pintype "power_in"))
      (node (ref "PFMF.050.1") (pin "2") (pinfunction "2_2") (pintype "passive"))
      (node (ref "Q1") (pin "1") (pinfunction "G_1") (pintype "bidirectional"))
      (node (ref "R1-PWRUSB") (pin "2") (pinfunction "2_2") (pintype "passive"))
      (node (ref "TP14") (pin "TP") (pinfunction "TP_TP") (pintype "input"))
    )
    (net (code "55") (name "VRTC") (class "Default")
      (node (ref "C10_SUPERCAP") (pin "1") (pinfunction "1_1") (pintype "passive"))
      (node (ref "C8") (pin "1") (pinfunction "1_1") (pintype "passive"))
      (node (ref "R_CAPACITOR") (pin "2") (pinfunction "2_2") (pintype "passive"))
      (node (ref "U3") (pin "14") (pinfunction "VBAT_14") (pintype "power_in"))
    )
    (net (code "56") (name "VUSB") (class "Default")
      (node (ref "J2") (pin "A4") (pinfunction "A4_A4") (pintype "bidirectional"))
      (node (ref "J2") (pin "A9") (pinfunction "A9_A9") (pintype "bidirectional"))
      (node (ref "J2") (pin "B4") (pinfunction "B4_B4") (pintype "bidirectional"))
      (node (ref "J2") (pin "B9") (pinfunction "B9_B9") (pintype "bidirectional"))
      (node (ref "PFMF.050.1") (pin "1") (pinfunction "1_1") (pintype "passive"))
    )
    (net (code "57") (name "unconnected-(IC1-NC-Pad4)") (class "Default")
      (node (ref "IC1") (pin "4") (pinfunction "NC_4") (pintype "no_connect"))
    )
    (net (code "58") (name "unconnected-(IC4-NC-Pad4)") (class "Default")
      (node (ref "IC4") (pin "4") (pinfunction "NC_4") (pintype "no_connect"))
    )
    (net (code "59") (name "unconnected-(J1-Pad1)") (class "Default")
      (node (ref "J1") (pin "1") (pinfunction "1_1") (pintype "bidirectional"))
    )
    (net (code "60") (name "unconnected-(J1-Pad6)") (class "Default")
      (node (ref "J1") (pin "6") (pinfunction "6_6") (pintype "bidirectional"))
    )
    (net (code "61") (name "unconnected-(J1-Pad7)") (class "Default")
      (node (ref "J1") (pin "7") (pinfunction "7_7") (pintype "bidirectional"))
    )
    (net (code "62") (name "unconnected-(J2-PadA8)") (class "Default")
      (node (ref "J2") (pin "A8") (pinfunction "A8_A8") (pintype "bidirectional"))
    )
    (net (code "63") (name "unconnected-(J2-PadB8)") (class "Default")
      (node (ref "J2") (pin "B8") (pinfunction "B8_B8") (pintype "bidirectional"))
    )
    (net (code "64") (name "unconnected-(J4-DAT1-PadP8)") (class "Default")
      (node (ref "J4") (pin "P8") (pinfunction "DAT1_P8") (pintype "bidirectional"))
    )
    (net (code "65") (name "unconnected-(J4-DAT2-PadP1)") (class "Default")
      (node (ref "J4") (pin "P1") (pinfunction "DAT2_P1") (pintype "bidirectional"))
    )
    (net (code "66") (name "unconnected-(J4-DETECTION_1-PadS1)") (class "Default")
      (node (ref "J4") (pin "S1") (pinfunction "DETECTION_1_S1") (pintype "bidirectional"))
    )
    (net (code "67") (name "unconnected-(J4-DETECTION_2-PadS2)") (class "Default")
      (node (ref "J4") (pin "S2") (pinfunction "DETECTION_2_S2") (pintype "bidirectional"))
    )
    (net (code "68") (name "unconnected-(U2-NC-Pad22)") (class "Default")
      (node (ref "U2") (pin "22") (pinfunction "NC_22") (pintype "no_connect"))
    )
    (net (code "69") (name "unconnected-(U4-~{ALERT}-Pad5)") (class "Default")
      (node (ref "U4") (pin "5") (pinfunction "~{ALERT}_5") (pintype "output"))
    )
  )
)
